# cpu_sheet.net
KiCad netlist of a schematic drawn in Altium Designer
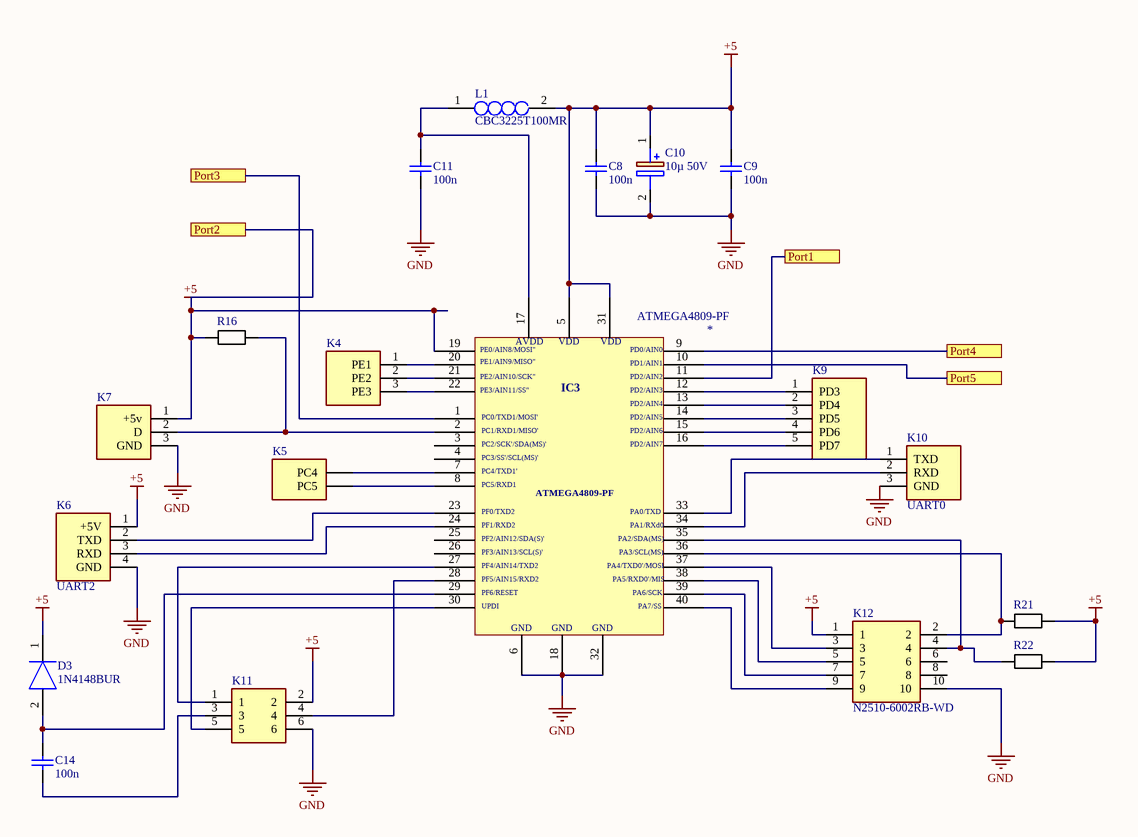
[diagram p0: cpu sheet.SchDoc]

(export (version "E")
  (design (tool "Eeschema 10.0.6"))
  (components
    (comp (ref "*")
      (value "ATMEGA4809-PF")
      (footprint "DIP1543W47P254L5321H635Q40")
      (libsource (lib "Schlib1") (part "ATMEGA4809-PF"))
    )
    (comp (ref "C8")
      (value "100n")
      (footprint "LIBRARYSOURCE=Vault")
      (fields
        (field (name "PART NUMBER") "02015A270JAT2A")
        (field (name "MANUFACTURER") "AVX Interconnect / Elco")
      )
      (libsource (lib "Schlib1") (part "CAP"))
    )
    (comp (ref "C9")
      (value "100n")
      (footprint "LIBRARYSOURCE=Vault")
      (fields
        (field (name "PART NUMBER") "02015A270JAT2A")
        (field (name "MANUFACTURER") "AVX Interconnect / Elco")
      )
      (libsource (lib "Schlib1") (part "CAP"))
    )
    (comp (ref "C10")
      (value "10µ 50V")
      (footprint "SamacSys:CAPPRD500W65D1025H1250")
      (description "Capacitor Polarised")
      (fields
        (field (name "MANUFACTURER_PART_NUMBER") "B41851A6227M000")
        (field (name "MOUSER PART NUMBER") "871-B41851A6227M000")
      )
      (libsource (lib "*") (part "B41851A6227M000"))
    )
    (comp (ref "C11")
      (value "100n")
      (footprint "LIBRARYSOURCE=Vault")
      (fields
        (field (name "PART NUMBER") "02015A270JAT2A")
        (field (name "MANUFACTURER") "AVX Interconnect / Elco")
      )
      (libsource (lib "Schlib1") (part "CAP"))
    )
    (comp (ref "C14")
      (value "100n")
      (footprint "LIBRARYSOURCE=Vault")
      (fields
        (field (name "PART NUMBER") "02015A270JAT2A")
        (field (name "MANUFACTURER") "AVX Interconnect / Elco")
      )
      (libsource (lib "Schlib1") (part "CAP"))
    )
    (comp (ref "D3")
      (value "1N4148BUR")
      (footprint "SamacSys:1N4148BUR")
      (description "Diode")
      (libsource (lib "Schlib1") (part "1N4148BUR"))
    )
    (comp (ref "K4")
      (value "10129378-903001BLF")
      (footprint "SamacSys:HDRV3W67P0X254_1X3_762X241X858P")
      (description "Connector")
      (fields (field (name "MOUSER PART NUMBER") "649-1012937890301BLF"))
      (libsource (lib "Schlib1") (part "10129378-903001BLF"))
    )
    (comp (ref "K5")
      (value "10129378-902001BLF")
      (footprint "SamacSys:HDRV2W67P0X254_1X2_508X241X843P")
      (description "Connector")
      (fields (field (name "MOUSER PART NUMBER") "649-1012937890201BLF"))
      (libsource (lib "Schlib1") (part "10129378-902001BLF"))
    )
    (comp (ref "K6")
      (value "UART2")
      (footprint "SamacSys:HDRV4W67P0X254_1X4_1270X241X858P")
      (description "Connector")
      (fields
        (field (name "MANUFACTURER_PART_NUMBER") "10129378-904001BLF")
        (field (name "MOUSER PART NUMBER") "649-1012937890401BLF")
      )
      (libsource (lib "Schlib1") (part "10129378-904001BLF"))
    )
    (comp (ref "K7")
      (value "10129378-903001BLF")
      (footprint "SamacSys:HDRV3W67P0X254_1X3_762X241X858P")
      (description "Connector")
      (fields (field (name "MOUSER PART NUMBER") "649-1012937890301BLF"))
      (libsource (lib "Schlib1") (part "10129378-903001BLF"))
    )
    (comp (ref "K9")
      (value "10129378-905001BLF")
      (footprint "SamacSys:HDRV5W67P0X254_1X5_1270X241X858P")
      (description "Connector")
      (fields (field (name "MOUSER PART NUMBER") "649-1012937890501BLF"))
      (libsource (lib "Schlib1") (part "10129378-905001BLF"))
    )
    (comp (ref "K10")
      (value "UART0")
      (footprint "SamacSys:HDRV3W67P0X254_1X3_762X241X858P")
      (description "Connector")
      (fields
        (field (name "MANUFACTURER_PART_NUMBER") "10129378-903001BLF")
        (field (name "MOUSER PART NUMBER") "649-1012937890301BLF")
      )
      (libsource (lib "") (part "10129378-903001BLF_1"))
    )
    (comp (ref "K11")
      (value "10129381-906002BLF")
      (footprint "SamacSys:HDRV6W67P254_2X3_762X483X858P")
      (description "Connector")
      (fields (field (name "MOUSER PART NUMBER") "649-1012938190602BLF"))
      (libsource (lib "Schlib1") (part "10129381-906002BLF"))
    )
    (comp (ref "K12")
      (value "N2510-6002RB-WD")
      (footprint "SamacSys:N25106002RBWD")
      (description "Connector")
      (fields (field (name "MOUSER PART NUMBER") "517-N2510-6002RB-WD"))
      (libsource (lib "Schlib1") (part "N2510-6002RB-WD"))
    )
    (comp (ref "L1")
      (value "CBC3225T100MR")
      (footprint "SamacSys:INDC3225X270N")
      (description "Inductor")
      (fields (field (name "MOUSER PART NUMBER") "963-CBC3225T100MR"))
      (libsource (lib "*") (part "CBC3225T100MR"))
    )
    (comp (ref "R16")
      (value "CRCW08050000Z0EA")
      (footprint "RESC2012X65N")
      (fields (field (name "MANUFACTURER") "Vishay Dale"))
      (libsource (lib "Schlib1") (part "RES"))
    )
    (comp (ref "R21")
      (value "CRCW08050000Z0EA")
      (footprint "RESC2012X65N")
      (fields (field (name "MANUFACTURER") "Vishay Dale"))
      (libsource (lib "Schlib1") (part "RES"))
    )
    (comp (ref "R22")
      (value "CRCW08050000Z0EA")
      (footprint "RESC2012X65N")
      (fields (field (name "MANUFACTURER") "Vishay Dale"))
      (libsource (lib "Schlib1") (part "RES"))
    )
  )
  (nets
    (net (code "1") (name "+5") (class "Default")
      (node (ref "*") (pin "19") (pinfunction "19_19") (pintype "passive"))
      (node (ref "*") (pin "31") (pinfunction "31_31") (pintype "passive"))
      (node (ref "*") (pin "5") (pinfunction "5_5") (pintype "passive"))
      (node (ref "C10") (pin "1") (pinfunction "+_1") (pintype "passive"))
      (node (ref "C8") (pin "2") (pinfunction "2_2") (pintype "passive"))
      (node (ref "C9") (pin "2") (pinfunction "2_2") (pintype "passive"))
      (node (ref "D3") (pin "1") (pinfunction "K_1") (pintype "passive"))
      (node (ref "K11") (pin "2") (pinfunction "2_2") (pintype "passive"))
      (node (ref "K12") (pin "1") (pinfunction "1_1") (pintype "passive"))
      (node (ref "K6") (pin "1") (pinfunction "+5V_1") (pintype "passive"))
      (node (ref "K7") (pin "1") (pinfunction "+5v_1") (pintype "passive"))
      (node (ref "L1") (pin "2") (pinfunction "2_2") (pintype "passive"))
      (node (ref "R16") (pin "1") (pinfunction "1_1") (pintype "passive"))
      (node (ref "R21") (pin "2") (pinfunction "2_2") (pintype "passive"))
      (node (ref "R22") (pin "2") (pinfunction "2_2") (pintype "passive"))
    )
    (net (code "2") (name "/Port1") (class "Default")
      (node (ref "*") (pin "11") (pinfunction "11_11") (pintype "passive"))
    )
    (net (code "3") (name "/Port3") (class "Default")
      (node (ref "*") (pin "1") (pinfunction "1_1") (pintype "passive"))
    )
    (net (code "4") (name "/Port4") (class "Default")
      (node (ref "*") (pin "9") (pinfunction "9_9") (pintype "passive"))
    )
    (net (code "5") (name "/Port5") (class "Default")
      (node (ref "*") (pin "10") (pinfunction "10_10") (pintype "passive"))
    )
    (net (code "6") (name "GND") (class "Default")
      (node (ref "*") (pin "18") (pinfunction "18_18") (pintype "passive"))
      (node (ref "*") (pin "32") (pinfunction "32_32") (pintype "passive"))
      (node (ref "*") (pin "6") (pinfunction "6_6") (pintype "passive"))
      (node (ref "C10") (pin "2") (pinfunction "-_2") (pintype "passive"))
      (node (ref "C11") (pin "1") (pinfunction "1_1") (pintype "passive"))
      (node (ref "C8") (pin "1") (pinfunction "1_1") (pintype "passive"))
      (node (ref "C9") (pin "1") (pinfunction "1_1") (pintype "passive"))
      (node (ref "K10") (pin "3") (pinfunction "GND_3") (pintype "passive"))
      (node (ref "K11") (pin "6") (pinfunction "6_6") (pintype "passive"))
      (node (ref "K12") (pin "10") (pinfunction "10_10") (pintype "passive"))
      (node (ref "K6") (pin "4") (pinfunction "GND_4") (pintype "passive"))
      (node (ref "K7") (pin "3") (pinfunction "GND_3") (pintype "passive"))
    )
    (net (code "7") (name "Net-(*-Pad7)") (class "Default")
      (node (ref "*") (pin "7") (pinfunction "7_7") (pintype "passive"))
      (node (ref "K5") (pin "PC4") (pinfunction "PC4_PC4") (pintype "passive"))
    )
    (net (code "8") (name "Net-(*-Pad8)") (class "Default")
      (node (ref "*") (pin "8") (pinfunction "8_8") (pintype "passive"))
      (node (ref "K5") (pin "PC5") (pinfunction "PC5_PC5") (pintype "passive"))
    )
    (net (code "9") (name "Net-(*-Pad17)") (class "Default")
      (node (ref "*") (pin "17") (pinfunction "17_17") (pintype "passive"))
      (node (ref "C11") (pin "2") (pinfunction "2_2") (pintype "passive"))
      (node (ref "L1") (pin "1") (pinfunction "1_1") (pintype "passive"))
    )
    (net (code "10") (name "Net-(*-Pad27)") (class "Default")
      (node (ref "*") (pin "27") (pinfunction "27_27") (pintype "passive"))
      (node (ref "K11") (pin "1") (pinfunction "1_1") (pintype "passive"))
    )
    (net (code "11") (name "Net-(*-Pad28)") (class "Default")
      (node (ref "*") (pin "28") (pinfunction "28_28") (pintype "passive"))
      (node (ref "K11") (pin "4") (pinfunction "4_4") (pintype "passive"))
    )
    (net (code "12") (name "Net-(*-Pad30)") (class "Default")
      (node (ref "*") (pin "30") (pinfunction "30_30") (pintype "passive"))
      (node (ref "K11") (pin "5") (pinfunction "5_5") (pintype "passive"))
    )
    (net (code "13") (name "Net-(*-Pad35)") (class "Default")
      (node (ref "*") (pin "35") (pinfunction "35_35") (pintype "passive"))
      (node (ref "K12") (pin "4") (pinfunction "4_4") (pintype "passive"))
      (node (ref "R22") (pin "1") (pinfunction "1_1") (pintype "passive"))
    )
    (net (code "14") (name "Net-(*-Pad36)") (class "Default")
      (node (ref "*") (pin "36") (pinfunction "36_36") (pintype "passive"))
      (node (ref "K12") (pin "2") (pinfunction "2_2") (pintype "passive"))
      (node (ref "R21") (pin "1") (pinfunction "1_1") (pintype "passive"))
    )
    (net (code "15") (name "Net-(*-Pad37)") (class "Default")
      (node (ref "*") (pin "37") (pinfunction "37_37") (pintype "passive"))
      (node (ref "K12") (pin "3") (pinfunction "3_3") (pintype "passive"))
    )
    (net (code "16") (name "Net-(*-Pad38)") (class "Default")
      (node (ref "*") (pin "38") (pinfunction "38_38") (pintype "passive"))
      (node (ref "K12") (pin "5") (pinfunction "5_5") (pintype "passive"))
    )
    (net (code "17") (name "Net-(*-Pad39)") (class "Default")
      (node (ref "*") (pin "39") (pinfunction "39_39") (pintype "passive"))
      (node (ref "K12") (pin "7") (pinfunction "7_7") (pintype "passive"))
    )
    (net (code "18") (name "Net-(*-Pad40)") (class "Default")
      (node (ref "*") (pin "40") (pinfunction "40_40") (pintype "passive"))
      (node (ref "K12") (pin "9") (pinfunction "9_9") (pintype "passive"))
    )
    (net (code "19") (name "Net-(C14-Pad1)") (class "Default")
      (node (ref "C14") (pin "1") (pinfunction "1_1") (pintype "passive"))
      (node (ref "K11") (pin "3") (pinfunction "3_3") (pintype "passive"))
    )
    (net (code "20") (name "Net-(D3-A)") (class "Default")
      (node (ref "*") (pin "29") (pinfunction "29_29") (pintype "passive"))
      (node (ref "C14") (pin "2") (pinfunction "2_2") (pintype "passive"))
      (node (ref "D3") (pin "2") (pinfunction "A_2") (pintype "passive"))
    )
    (net (code "21") (name "Net-(K4-+5v)") (class "Default")
      (node (ref "*") (pin "20") (pinfunction "20_20") (pintype "passive"))
      (node (ref "K4") (pin "1") (pinfunction "+5v_1") (pintype "passive"))
    )
    (net (code "22") (name "Net-(K4-D)") (class "Default")
      (node (ref "*") (pin "21") (pinfunction "21_21") (pintype "passive"))
      (node (ref "K4") (pin "2") (pinfunction "D_2") (pintype "passive"))
    )
    (net (code "23") (name "Net-(K4-GND)") (class "Default")
      (node (ref "*") (pin "22") (pinfunction "22_22") (pintype "passive"))
      (node (ref "K4") (pin "3") (pinfunction "GND_3") (pintype "passive"))
    )
    (net (code "24") (name "Net-(K6-RXD)") (class "Default")
      (node (ref "*") (pin "24") (pinfunction "24_24") (pintype "passive"))
      (node (ref "K6") (pin "3") (pinfunction "RXD_3") (pintype "passive"))
    )
    (net (code "25") (name "Net-(K6-TXD)") (class "Default")
      (node (ref "*") (pin "23") (pinfunction "23_23") (pintype "passive"))
      (node (ref "K6") (pin "2") (pinfunction "TXD_2") (pintype "passive"))
    )
    (net (code "26") (name "Net-(K7-D)") (class "Default")
      (node (ref "*") (pin "2") (pinfunction "2_2") (pintype "passive"))
      (node (ref "K7") (pin "2") (pinfunction "D_2") (pintype "passive"))
      (node (ref "R16") (pin "2") (pinfunction "2_2") (pintype "passive"))
    )
    (net (code "27") (name "Net-(K9-PD3)") (class "Default")
      (node (ref "*") (pin "12") (pinfunction "12_12") (pintype "passive"))
      (node (ref "K9") (pin "1") (pinfunction "PD3_1") (pintype "passive"))
    )
    (net (code "28") (name "Net-(K9-PD4)") (class "Default")
      (node (ref "*") (pin "13") (pinfunction "13_13") (pintype "passive"))
      (node (ref "K9") (pin "2") (pinfunction "PD4_2") (pintype "passive"))
    )
    (net (code "29") (name "Net-(K9-PD5)") (class "Default")
      (node (ref "*") (pin "14") (pinfunction "14_14") (pintype "passive"))
      (node (ref "K9") (pin "3") (pinfunction "PD5_3") (pintype "passive"))
    )
    (net (code "30") (name "Net-(K9-PD6)") (class "Default")
      (node (ref "*") (pin "15") (pinfunction "15_15") (pintype "passive"))
      (node (ref "K9") (pin "4") (pinfunction "PD6_4") (pintype "passive"))
    )
    (net (code "31") (name "Net-(K9-PD7)") (class "Default")
      (node (ref "*") (pin "16") (pinfunction "16_16") (pintype "passive"))
      (node (ref "K9") (pin "5") (pinfunction "PD7_5") (pintype "passive"))
    )
    (net (code "32") (name "Net-(K10-RXD)") (class "Default")
      (node (ref "*") (pin "34") (pinfunction "34_34") (pintype "passive"))
      (node (ref "K10") (pin "2") (pinfunction "RXD_2") (pintype "passive"))
    )
    (net (code "33") (name "Net-(K10-TXD)") (class "Default")
      (node (ref "*") (pin "33") (pinfunction "33_33") (pintype "passive"))
      (node (ref "K10") (pin "1") (pinfunction "TXD_1") (pintype "passive"))
    )
    (net (code "34") (name "unconnected-(*-Pad3)") (class "Default")
      (node (ref "*") (pin "3") (pinfunction "3_3") (pintype "passive"))
    )
    (net (code "35") (name "unconnected-(*-Pad4)") (class "Default")
      (node (ref "*") (pin "4") (pinfunction "4_4") (pintype "passive"))
    )
    (net (code "36") (name "unconnected-(*-Pad25)") (class "Default")
      (node (ref "*") (pin "25") (pinfunction "25_25") (pintype "passive"))
    )
    (net (code "37") (name "unconnected-(*-Pad26)") (class "Default")
      (node (ref "*") (pin "26") (pinfunction "26_26") (pintype "passive"))
    )
    (net (code "38") (name "unconnected-(K12-Pad6)") (class "Default")
      (node (ref "K12") (pin "6") (pinfunction "6_6") (pintype "passive"))
    )
    (net (code "39") (name "unconnected-(K12-Pad8)") (class "Default")
      (node (ref "K12") (pin "8") (pinfunction "8_8") (pintype "passive"))
    )
  )
)
